# measurement.net
KiCad netlist of a schematic drawn in EAGLE
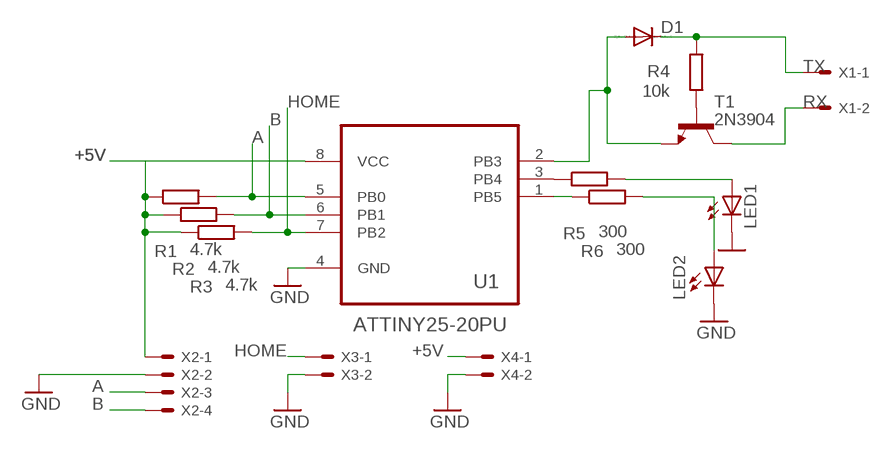
[diagram p0: schematic, sheet 1]

(export (version "E")
  (design (tool "Eeschema 10.0.6"))
  (components
    (comp (ref "D1")
      (value "1N4148DO35-7")
      (footprint "eagle-import:DO35-7")
      (libsource (lib "eagle-import") (part "1N4148DO35-7"))
    )
    (comp (ref "LED1")
      (value "LED5MM")
      (footprint "eagle-import:LED5MM")
      (libsource (lib "eagle-import") (part "LED5MM"))
    )
    (comp (ref "LED2")
      (value "LED5MM")
      (footprint "eagle-import:LED5MM")
      (libsource (lib "eagle-import") (part "LED5MM"))
    )
    (comp (ref "R1")
      (value "4.7k")
      (footprint "eagle-import:0414V")
      (libsource (lib "eagle-import") (part "R-EU_0414/5V"))
    )
    (comp (ref "R2")
      (value "4.7k")
      (footprint "eagle-import:0414V")
      (libsource (lib "eagle-import") (part "R-EU_0414/5V"))
    )
    (comp (ref "R3")
      (value "4.7k")
      (footprint "eagle-import:0414V")
      (libsource (lib "eagle-import") (part "R-EU_0414/5V"))
    )
    (comp (ref "R4")
      (value "10k")
      (footprint "eagle-import:0414V")
      (libsource (lib "eagle-import") (part "R-EU_0414/5V"))
    )
    (comp (ref "R5")
      (value "300")
      (footprint "eagle-import:0414V")
      (libsource (lib "eagle-import") (part "R-EU_0414/5V"))
    )
    (comp (ref "R6")
      (value "300")
      (footprint "eagle-import:0414V")
      (libsource (lib "eagle-import") (part "R-EU_0414/5V"))
    )
    (comp (ref "T1")
      (value "2N3904")
      (footprint "eagle-import:TO92")
      (libsource (lib "eagle-import") (part "2N3904"))
    )
    (comp (ref "U1")
      (value "ATTINY25-20PU")
      (footprint "eagle-import:DIP254P762X533-8")
      (fields (field (name "MF") "Microchip"))
      (libsource (lib "eagle-import") (part "ATTINY25-20PU"))
    )
    (comp (ref "X1")
      (value "5566-2")
      (footprint "eagle-import:5566-2")
      (fields (field (name "MF") "MOLEX"))
      (libsource (lib "eagle-import") (part "5566-2"))
    )
    (comp (ref "X2")
      (value "5566-4")
      (footprint "eagle-import:5566-4")
      (fields (field (name "MF") "MOLEX"))
      (libsource (lib "eagle-import") (part "5566-4"))
    )
    (comp (ref "X3")
      (value "5566-2")
      (footprint "eagle-import:5566-2")
      (fields (field (name "MF") "MOLEX"))
      (libsource (lib "eagle-import") (part "5566-2"))
    )
    (comp (ref "X4")
      (value "5566-2")
      (footprint "eagle-import:5566-2")
      (fields (field (name "MF") "MOLEX"))
      (libsource (lib "eagle-import") (part "5566-2"))
    )
  )
  (nets
    (net (code "1") (name "/+5V") (class "Default")
      (node (ref "R1") (pin "1") (pinfunction "1_1") (pintype "passive"))
      (node (ref "R2") (pin "1") (pinfunction "1_1") (pintype "passive"))
      (node (ref "R3") (pin "1") (pinfunction "1_1") (pintype "passive"))
      (node (ref "U1") (pin "8") (pinfunction "VCC_8") (pintype "power_in"))
      (node (ref "X2") (pin "1") (pinfunction "S_1") (pintype "passive"))
      (node (ref "X4") (pin "1") (pinfunction "S_1") (pintype "passive"))
    )
    (net (code "2") (name "/A") (class "Default")
      (node (ref "R1") (pin "2") (pinfunction "2_2") (pintype "passive"))
      (node (ref "U1") (pin "5") (pinfunction "PB0_5") (pintype "bidirectional"))
      (node (ref "X2") (pin "3") (pinfunction "S_3") (pintype "passive"))
    )
    (net (code "3") (name "/B") (class "Default")
      (node (ref "R2") (pin "2") (pinfunction "2_2") (pintype "passive"))
      (node (ref "U1") (pin "6") (pinfunction "PB1_6") (pintype "bidirectional"))
      (node (ref "X2") (pin "4") (pinfunction "S_4") (pintype "passive"))
    )
    (net (code "4") (name "/HOME") (class "Default")
      (node (ref "R3") (pin "2") (pinfunction "2_2") (pintype "passive"))
      (node (ref "U1") (pin "7") (pinfunction "PB2_7") (pintype "bidirectional"))
      (node (ref "X3") (pin "1") (pinfunction "S_1") (pintype "passive"))
    )
    (net (code "5") (name "/RX") (class "Default")
      (node (ref "T1") (pin "1") (pinfunction "C_1") (pintype "passive"))
      (node (ref "X1") (pin "2") (pinfunction "S_2") (pintype "passive"))
    )
    (net (code "6") (name "/TX") (class "Default")
      (node (ref "D1") (pin "C") (pinfunction "C_C") (pintype "passive"))
      (node (ref "R4") (pin "2") (pinfunction "2_2") (pintype "passive"))
      (node (ref "X1") (pin "1") (pinfunction "S_1") (pintype "passive"))
    )
    (net (code "7") (name "GND") (class "Default")
      (node (ref "LED1") (pin "K") (pinfunction "C_K") (pintype "passive"))
      (node (ref "LED2") (pin "K") (pinfunction "C_K") (pintype "passive"))
      (node (ref "U1") (pin "4") (pinfunction "GND_4") (pintype "passive"))
      (node (ref "X2") (pin "2") (pinfunction "S_2") (pintype "passive"))
      (node (ref "X3") (pin "2") (pinfunction "S_2") (pintype "passive"))
      (node (ref "X4") (pin "2") (pinfunction "S_2") (pintype "passive"))
    )
    (net (code "8") (name "Net-(LED1-PadA)") (class "Default")
      (node (ref "LED1") (pin "A") (pinfunction "A_A") (pintype "passive"))
      (node (ref "R5") (pin "2") (pinfunction "2_2") (pintype "passive"))
    )
    (net (code "9") (name "Net-(LED2-PadA)") (class "Default")
      (node (ref "LED2") (pin "A") (pinfunction "A_A") (pintype "passive"))
      (node (ref "R6") (pin "2") (pinfunction "2_2") (pintype "passive"))
    )
    (net (code "10") (name "Net-(T1-B)") (class "Default")
      (node (ref "R4") (pin "1") (pinfunction "1_1") (pintype "passive"))
      (node (ref "T1") (pin "2") (pinfunction "B_2") (pintype "passive"))
    )
    (net (code "11") (name "Net-(T1-E)") (class "Default")
      (node (ref "D1") (pin "A") (pinfunction "A_A") (pintype "passive"))
      (node (ref "T1") (pin "3") (pinfunction "E_3") (pintype "passive"))
      (node (ref "U1") (pin "2") (pinfunction "PB3_2") (pintype "bidirectional"))
    )
    (net (code "12") (name "Net-(U1-PB4)") (class "Default")
      (node (ref "R5") (pin "1") (pinfunction "1_1") (pintype "passive"))
      (node (ref "U1") (pin "3") (pinfunction "PB4_3") (pintype "bidirectional"))
    )
    (net (code "13") (name "Net-(U1-PB5)") (class "Default")
      (node (ref "R6") (pin "1") (pinfunction "1_1") (pintype "passive"))
      (node (ref "U1") (pin "1") (pinfunction "PB5_1") (pintype "bidirectional"))
    )
  )
)
